# IO_SchDoc.net
KiCad netlist of a schematic drawn in Altium Designer
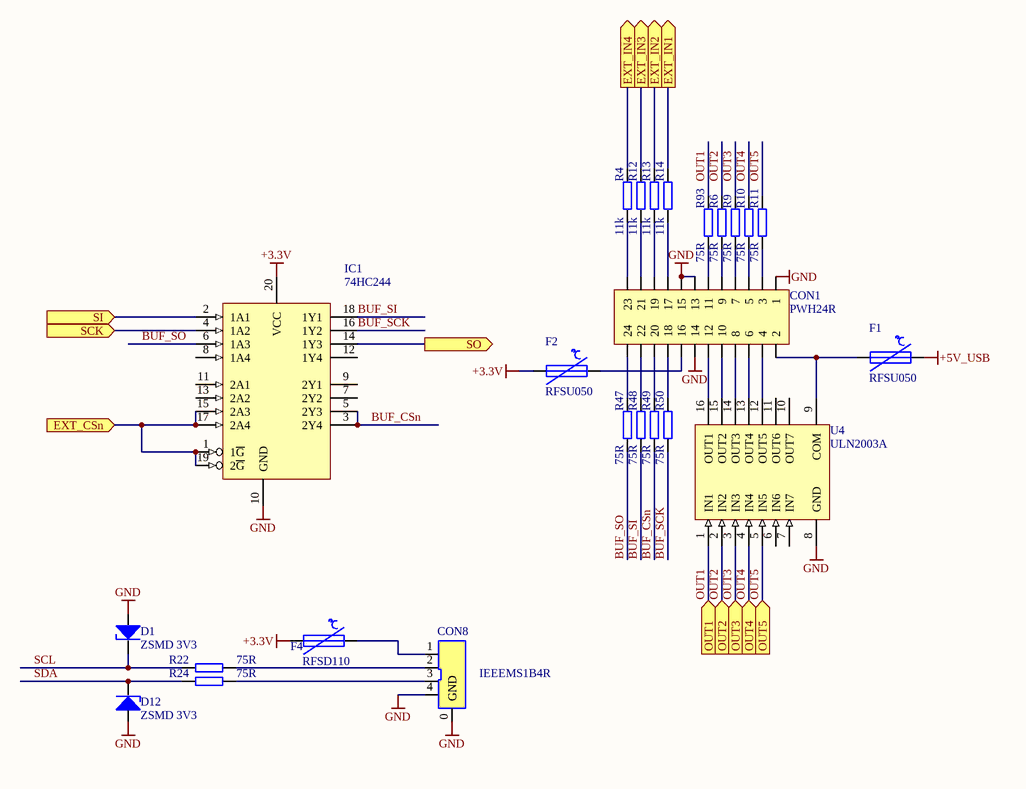
[diagram p0: IO_SchDoc.SchDoc]

(export (version "E")
  (design (tool "Eeschema 10.0.6"))
  (components
    (comp (ref "CON1")
      (value "PWH24R")
      (footprint "CON_PWH24R-LF")
      (description "3mm crimped terminal (Maritex)")
      (libsource (lib "LIBRARY_SCH") (part "CON_crimp_24p_RA_TH_3mm"))
    )
    (comp (ref "CON8")
      (value "IEEEMS1B4R")
      (footprint "CON_IEEEMS1B4R")
      (description "CON_IEEE1394_mini")
      (libsource (lib "LIBRARY_SCH") (part "CON_USB_mini"))
    )
    (comp (ref "D1")
      (value "ZSMD 3V3")
      (footprint "SOD80")
      (description "Zener Diode")
      (libsource (lib "*") (part "D_ZENER"))
    )
    (comp (ref "D12")
      (value "ZSMD 3V3")
      (footprint "SOD80")
      (description "Zener Diode")
      (libsource (lib "*") (part "D_ZENER"))
    )
    (comp (ref "F1")
      (value "RFSU050")
      (footprint "PTC_SMD_1812")
      (description "polymer FUSE")
      (libsource (lib "LIBRARY_SCH") (part "F_POLYSWITCH"))
    )
    (comp (ref "F2")
      (value "RFSU050")
      (footprint "PTC_SMD_1812")
      (description "polymer FUSE")
      (libsource (lib "LIBRARY_SCH") (part "F_POLYSWITCH"))
    )
    (comp (ref "F4")
      (value "RFSD110")
      (footprint "PTC_SMD_1812")
      (description "polymer FUSE (Maritex)")
      (libsource (lib "LIBRARY_SCH") (part "F_POLYSWITCH"))
    )
    (comp (ref "IC1")
      (value "74HC244")
      (footprint "tssop20")
      (description "TTL BUS tristate")
      (libsource (lib "LIBRARY_SCH") (part "74HC244"))
    )
    (comp (ref "R4")
      (value "11k")
      (footprint "0603")
      (description "SMD Resistor")
      (libsource (lib "*") (part "RES_SMD"))
    )
    (comp (ref "R6")
      (value "75R")
      (footprint "0603")
      (description "SMD Resistor")
      (libsource (lib "*") (part "RES_SMD"))
    )
    (comp (ref "R9")
      (value "75R")
      (footprint "0603")
      (description "SMD Resistor")
      (libsource (lib "*") (part "RES_SMD"))
    )
    (comp (ref "R10")
      (value "75R")
      (footprint "0603")
      (description "SMD Resistor")
      (libsource (lib "*") (part "RES_SMD"))
    )
    (comp (ref "R11")
      (value "75R")
      (footprint "0603")
      (description "SMD Resistor")
      (libsource (lib "*") (part "RES_SMD"))
    )
    (comp (ref "R12")
      (value "11k")
      (footprint "0603")
      (description "SMD Resistor")
      (libsource (lib "*") (part "RES_SMD"))
    )
    (comp (ref "R13")
      (value "11k")
      (footprint "0603")
      (description "SMD Resistor")
      (libsource (lib "*") (part "RES_SMD"))
    )
    (comp (ref "R14")
      (value "11k")
      (footprint "0603")
      (description "SMD Resistor")
      (libsource (lib "*") (part "RES_SMD"))
    )
    (comp (ref "R22")
      (value "75R")
      (footprint "0603")
      (description "SMD Resistor")
      (libsource (lib "*") (part "RES_SMD"))
    )
    (comp (ref "R24")
      (value "75R")
      (footprint "0603")
      (description "SMD Resistor")
      (libsource (lib "*") (part "RES_SMD"))
    )
    (comp (ref "R47")
      (value "75R")
      (footprint "0603")
      (description "SMD Resistor")
      (libsource (lib "*") (part "RES_SMD"))
    )
    (comp (ref "R48")
      (value "75R")
      (footprint "0603")
      (description "SMD Resistor")
      (libsource (lib "*") (part "RES_SMD"))
    )
    (comp (ref "R49")
      (value "75R")
      (footprint "0603")
      (description "SMD Resistor")
      (libsource (lib "*") (part "RES_SMD"))
    )
    (comp (ref "R50")
      (value "75R")
      (footprint "0603")
      (description "SMD Resistor")
      (libsource (lib "*") (part "RES_SMD"))
    )
    (comp (ref "R93")
      (value "75R")
      (footprint "0603")
      (description "SMD Resistor")
      (libsource (lib "*") (part "RES_SMD"))
    )
    (comp (ref "U4")
      (value "ULN2003A")
      (footprint "So-16")
      (description "High-Voltage, High-Current Darlington Array")
      (fields (field (name "PUBLISHER") "Altium Limited"))
      (libsource (lib "*") (part "DRV_ULN2003A"))
    )
  )
  (nets
    (net (code "1") (name "+3.3V") (class "Default")
      (node (ref "F2") (pin "1") (pinfunction "1_1") (pintype "passive"))
      (node (ref "F4") (pin "1") (pinfunction "1_1") (pintype "passive"))
      (node (ref "IC1") (pin "20") (pinfunction "VCC_20") (pintype "power_in"))
    )
    (net (code "2") (name "+5V_USB") (class "Default")
      (node (ref "F1") (pin "2") (pinfunction "2_2") (pintype "passive"))
    )
    (net (code "3") (name "/BUF_CSn") (class "Default")
      (node (ref "IC1") (pin "3") (pinfunction "2Y4_3") (pintype "tri_state"))
      (node (ref "IC1") (pin "5") (pinfunction "2Y3_5") (pintype "tri_state"))
      (node (ref "R49") (pin "2") (pinfunction "2_2") (pintype "passive"))
    )
    (net (code "4") (name "/BUF_SCK") (class "Default")
      (node (ref "IC1") (pin "16") (pinfunction "1Y2_16") (pintype "tri_state"))
      (node (ref "R50") (pin "2") (pinfunction "2_2") (pintype "passive"))
    )
    (net (code "5") (name "/BUF_SI") (class "Default")
      (node (ref "IC1") (pin "18") (pinfunction "1Y1_18") (pintype "tri_state"))
      (node (ref "R48") (pin "2") (pinfunction "2_2") (pintype "passive"))
    )
    (net (code "6") (name "/BUF_SO") (class "Default")
      (node (ref "IC1") (pin "6") (pinfunction "1A3_6") (pintype "input"))
      (node (ref "R47") (pin "2") (pinfunction "2_2") (pintype "passive"))
    )
    (net (code "7") (name "/EXT_CSn") (class "Default")
      (node (ref "IC1") (pin "1") (pinfunction "1~{G}_1") (pintype "input"))
      (node (ref "IC1") (pin "15") (pinfunction "2A3_15") (pintype "input"))
      (node (ref "IC1") (pin "17") (pinfunction "2A4_17") (pintype "input"))
      (node (ref "IC1") (pin "19") (pinfunction "2~{G}_19") (pintype "input"))
    )
    (net (code "8") (name "/EXT_IN1") (class "Default")
      (node (ref "R14") (pin "1") (pinfunction "1_1") (pintype "passive"))
    )
    (net (code "9") (name "/EXT_IN2") (class "Default")
      (node (ref "R13") (pin "1") (pinfunction "1_1") (pintype "passive"))
    )
    (net (code "10") (name "/EXT_IN3") (class "Default")
      (node (ref "R12") (pin "1") (pinfunction "1_1") (pintype "passive"))
    )
    (net (code "11") (name "/EXT_IN4") (class "Default")
      (node (ref "R4") (pin "1") (pinfunction "1_1") (pintype "passive"))
    )
    (net (code "12") (name "/OUT1") (class "Default")
      (node (ref "R93") (pin "2") (pinfunction "2_2") (pintype "passive"))
      (node (ref "U4") (pin "1") (pinfunction "IN1_1") (pintype "input"))
    )
    (net (code "13") (name "/OUT2") (class "Default")
      (node (ref "R6") (pin "2") (pinfunction "2_2") (pintype "passive"))
      (node (ref "U4") (pin "2") (pinfunction "IN2_2") (pintype "input"))
    )
    (net (code "14") (name "/OUT3") (class "Default")
      (node (ref "R9") (pin "2") (pinfunction "2_2") (pintype "passive"))
      (node (ref "U4") (pin "3") (pinfunction "IN3_3") (pintype "input"))
    )
    (net (code "15") (name "/OUT4") (class "Default")
      (node (ref "R10") (pin "2") (pinfunction "2_2") (pintype "passive"))
      (node (ref "U4") (pin "4") (pinfunction "IN4_4") (pintype "input"))
    )
    (net (code "16") (name "/OUT5") (class "Default")
      (node (ref "R11") (pin "2") (pinfunction "2_2") (pintype "passive"))
      (node (ref "U4") (pin "5") (pinfunction "IN5_5") (pintype "input"))
    )
    (net (code "17") (name "/SCK") (class "Default")
      (node (ref "IC1") (pin "4") (pinfunction "1A2_4") (pintype "input"))
    )
    (net (code "18") (name "/SCL") (class "Default")
      (node (ref "D1") (pin "K") (pinfunction "K_K") (pintype "passive"))
      (node (ref "R22") (pin "1") (pinfunction "1_1") (pintype "passive"))
    )
    (net (code "19") (name "/SDA") (class "Default")
      (node (ref "D12") (pin "K") (pinfunction "K_K") (pintype "passive"))
      (node (ref "R24") (pin "1") (pinfunction "1_1") (pintype "passive"))
    )
    (net (code "20") (name "/SI") (class "Default")
      (node (ref "IC1") (pin "2") (pinfunction "1A1_2") (pintype "input"))
    )
    (net (code "21") (name "/SO") (class "Default")
      (node (ref "IC1") (pin "14") (pinfunction "1Y3_14") (pintype "tri_state"))
    )
    (net (code "22") (name "GND") (class "Default")
      (node (ref "CON1") (pin "1") (pinfunction "1_1") (pintype "passive"))
      (node (ref "CON1") (pin "13") (pinfunction "13_13") (pintype "passive"))
      (node (ref "CON1") (pin "14") (pinfunction "14_14") (pintype "passive"))
      (node (ref "CON1") (pin "15") (pinfunction "15_15") (pintype "passive"))
      (node (ref "CON8") (pin "0") (pinfunction "GND_0") (pintype "passive"))
      (node (ref "CON8") (pin "4") (pinfunction "4_4") (pintype "passive"))
      (node (ref "D1") (pin "A") (pinfunction "A_A") (pintype "passive"))
      (node (ref "D12") (pin "A") (pinfunction "A_A") (pintype "passive"))
      (node (ref "IC1") (pin "10") (pinfunction "GND_10") (pintype "power_in"))
      (node (ref "U4") (pin "8") (pinfunction "GND_8") (pintype "power_in"))
    )
    (net (code "23") (name "Net-(CON1-Pad3)") (class "Default")
      (node (ref "CON1") (pin "3") (pinfunction "3_3") (pintype "passive"))
      (node (ref "R11") (pin "1") (pinfunction "1_1") (pintype "passive"))
    )
    (net (code "24") (name "Net-(CON1-Pad5)") (class "Default")
      (node (ref "CON1") (pin "5") (pinfunction "5_5") (pintype "passive"))
      (node (ref "R10") (pin "1") (pinfunction "1_1") (pintype "passive"))
    )
    (net (code "25") (name "Net-(CON1-Pad7)") (class "Default")
      (node (ref "CON1") (pin "7") (pinfunction "7_7") (pintype "passive"))
      (node (ref "R9") (pin "1") (pinfunction "1_1") (pintype "passive"))
    )
    (net (code "26") (name "Net-(CON1-Pad9)") (class "Default")
      (node (ref "CON1") (pin "9") (pinfunction "9_9") (pintype "passive"))
      (node (ref "R6") (pin "1") (pinfunction "1_1") (pintype "passive"))
    )
    (net (code "27") (name "Net-(CON1-Pad11)") (class "Default")
      (node (ref "CON1") (pin "11") (pinfunction "11_11") (pintype "passive"))
      (node (ref "R93") (pin "1") (pinfunction "1_1") (pintype "passive"))
    )
    (net (code "28") (name "Net-(CON1-Pad16)") (class "Default")
      (node (ref "CON1") (pin "16") (pinfunction "16_16") (pintype "passive"))
      (node (ref "F2") (pin "2") (pinfunction "2_2") (pintype "passive"))
    )
    (net (code "29") (name "Net-(CON1-Pad17)") (class "Default")
      (node (ref "CON1") (pin "17") (pinfunction "17_17") (pintype "passive"))
      (node (ref "R14") (pin "2") (pinfunction "2_2") (pintype "passive"))
    )
    (net (code "30") (name "Net-(CON1-Pad18)") (class "Default")
      (node (ref "CON1") (pin "18") (pinfunction "18_18") (pintype "passive"))
      (node (ref "R50") (pin "1") (pinfunction "1_1") (pintype "passive"))
    )
    (net (code "31") (name "Net-(CON1-Pad19)") (class "Default")
      (node (ref "CON1") (pin "19") (pinfunction "19_19") (pintype "passive"))
      (node (ref "R13") (pin "2") (pinfunction "2_2") (pintype "passive"))
    )
    (net (code "32") (name "Net-(CON1-Pad20)") (class "Default")
      (node (ref "CON1") (pin "20") (pinfunction "20_20") (pintype "passive"))
      (node (ref "R49") (pin "1") (pinfunction "1_1") (pintype "passive"))
    )
    (net (code "33") (name "Net-(CON1-Pad21)") (class "Default")
      (node (ref "CON1") (pin "21") (pinfunction "21_21") (pintype "passive"))
      (node (ref "R12") (pin "2") (pinfunction "2_2") (pintype "passive"))
    )
    (net (code "34") (name "Net-(CON1-Pad22)") (class "Default")
      (node (ref "CON1") (pin "22") (pinfunction "22_22") (pintype "passive"))
      (node (ref "R48") (pin "1") (pinfunction "1_1") (pintype "passive"))
    )
    (net (code "35") (name "Net-(CON1-Pad23)") (class "Default")
      (node (ref "CON1") (pin "23") (pinfunction "23_23") (pintype "passive"))
      (node (ref "R4") (pin "2") (pinfunction "2_2") (pintype "passive"))
    )
    (net (code "36") (name "Net-(CON1-Pad24)") (class "Default")
      (node (ref "CON1") (pin "24") (pinfunction "24_24") (pintype "passive"))
      (node (ref "R47") (pin "1") (pinfunction "1_1") (pintype "passive"))
    )
    (net (code "37") (name "Net-(CON8-Pad1)") (class "Default")
      (node (ref "CON8") (pin "1") (pinfunction "1_1") (pintype "passive"))
      (node (ref "F4") (pin "2") (pinfunction "2_2") (pintype "passive"))
    )
    (net (code "38") (name "Net-(CON8-Pad2)") (class "Default")
      (node (ref "CON8") (pin "2") (pinfunction "2_2") (pintype "passive"))
      (node (ref "R22") (pin "2") (pinfunction "2_2") (pintype "passive"))
    )
    (net (code "39") (name "Net-(CON8-Pad3)") (class "Default")
      (node (ref "CON8") (pin "3") (pinfunction "3_3") (pintype "passive"))
      (node (ref "R24") (pin "2") (pinfunction "2_2") (pintype "passive"))
    )
    (net (code "40") (name "Net-(U4-COM)") (class "Default")
      (node (ref "CON1") (pin "2") (pinfunction "2_2") (pintype "passive"))
      (node (ref "F1") (pin "1") (pinfunction "1_1") (pintype "passive"))
      (node (ref "U4") (pin "9") (pinfunction "COM_9") (pintype "passive"))
    )
    (net (code "41") (name "Net-(U4-OUT1)") (class "Default")
      (node (ref "CON1") (pin "12") (pinfunction "12_12") (pintype "passive"))
      (node (ref "U4") (pin "16") (pinfunction "OUT1_16") (pintype "open_collector"))
    )
    (net (code "42") (name "Net-(U4-OUT2)") (class "Default")
      (node (ref "CON1") (pin "10") (pinfunction "10_10") (pintype "passive"))
      (node (ref "U4") (pin "15") (pinfunction "OUT2_15") (pintype "open_collector"))
    )
    (net (code "43") (name "Net-(U4-OUT3)") (class "Default")
      (node (ref "CON1") (pin "8") (pinfunction "8_8") (pintype "passive"))
      (node (ref "U4") (pin "14") (pinfunction "OUT3_14") (pintype "open_collector"))
    )
    (net (code "44") (name "Net-(U4-OUT4)") (class "Default")
      (node (ref "CON1") (pin "6") (pinfunction "6_6") (pintype "passive"))
      (node (ref "U4") (pin "13") (pinfunction "OUT4_13") (pintype "open_collector"))
    )
    (net (code "45") (name "Net-(U4-OUT5)") (class "Default")
      (node (ref "CON1") (pin "4") (pinfunction "4_4") (pintype "passive"))
      (node (ref "U4") (pin "12") (pinfunction "OUT5_12") (pintype "open_collector"))
    )
    (net (code "46") (name "unconnected-(IC1-1A4-Pad8)") (class "Default")
      (node (ref "IC1") (pin "8") (pinfunction "1A4_8") (pintype "input"))
    )
    (net (code "47") (name "unconnected-(IC1-1Y4-Pad12)") (class "Default")
      (node (ref "IC1") (pin "12") (pinfunction "1Y4_12") (pintype "tri_state"))
    )
    (net (code "48") (name "unconnected-(IC1-2A1-Pad11)") (class "Default")
      (node (ref "IC1") (pin "11") (pinfunction "2A1_11") (pintype "input"))
    )
    (net (code "49") (name "unconnected-(IC1-2A2-Pad13)") (class "Default")
      (node (ref "IC1") (pin "13") (pinfunction "2A2_13") (pintype "input"))
    )
    (net (code "50") (name "unconnected-(IC1-2Y1-Pad9)") (class "Default")
      (node (ref "IC1") (pin "9") (pinfunction "2Y1_9") (pintype "tri_state"))
    )
    (net (code "51") (name "unconnected-(IC1-2Y2-Pad7)") (class "Default")
      (node (ref "IC1") (pin "7") (pinfunction "2Y2_7") (pintype "tri_state"))
    )
    (net (code "52") (name "unconnected-(U4-IN6-Pad6)") (class "Default")
      (node (ref "U4") (pin "6") (pinfunction "IN6_6") (pintype "input"))
    )
    (net (code "53") (name "unconnected-(U4-IN7-Pad7)") (class "Default")
      (node (ref "U4") (pin "7") (pinfunction "IN7_7") (pintype "input"))
    )
    (net (code "54") (name "unconnected-(U4-OUT6-Pad11)") (class "Default")
      (node (ref "U4") (pin "11") (pinfunction "OUT6_11") (pintype "open_collector"))
    )
    (net (code "55") (name "unconnected-(U4-OUT7-Pad10)") (class "Default")
      (node (ref "U4") (pin "10") (pinfunction "OUT7_10") (pintype "open_collector"))
    )
  )
)
